# eMMC.net
KiCad netlist of a schematic drawn in Altium Designer
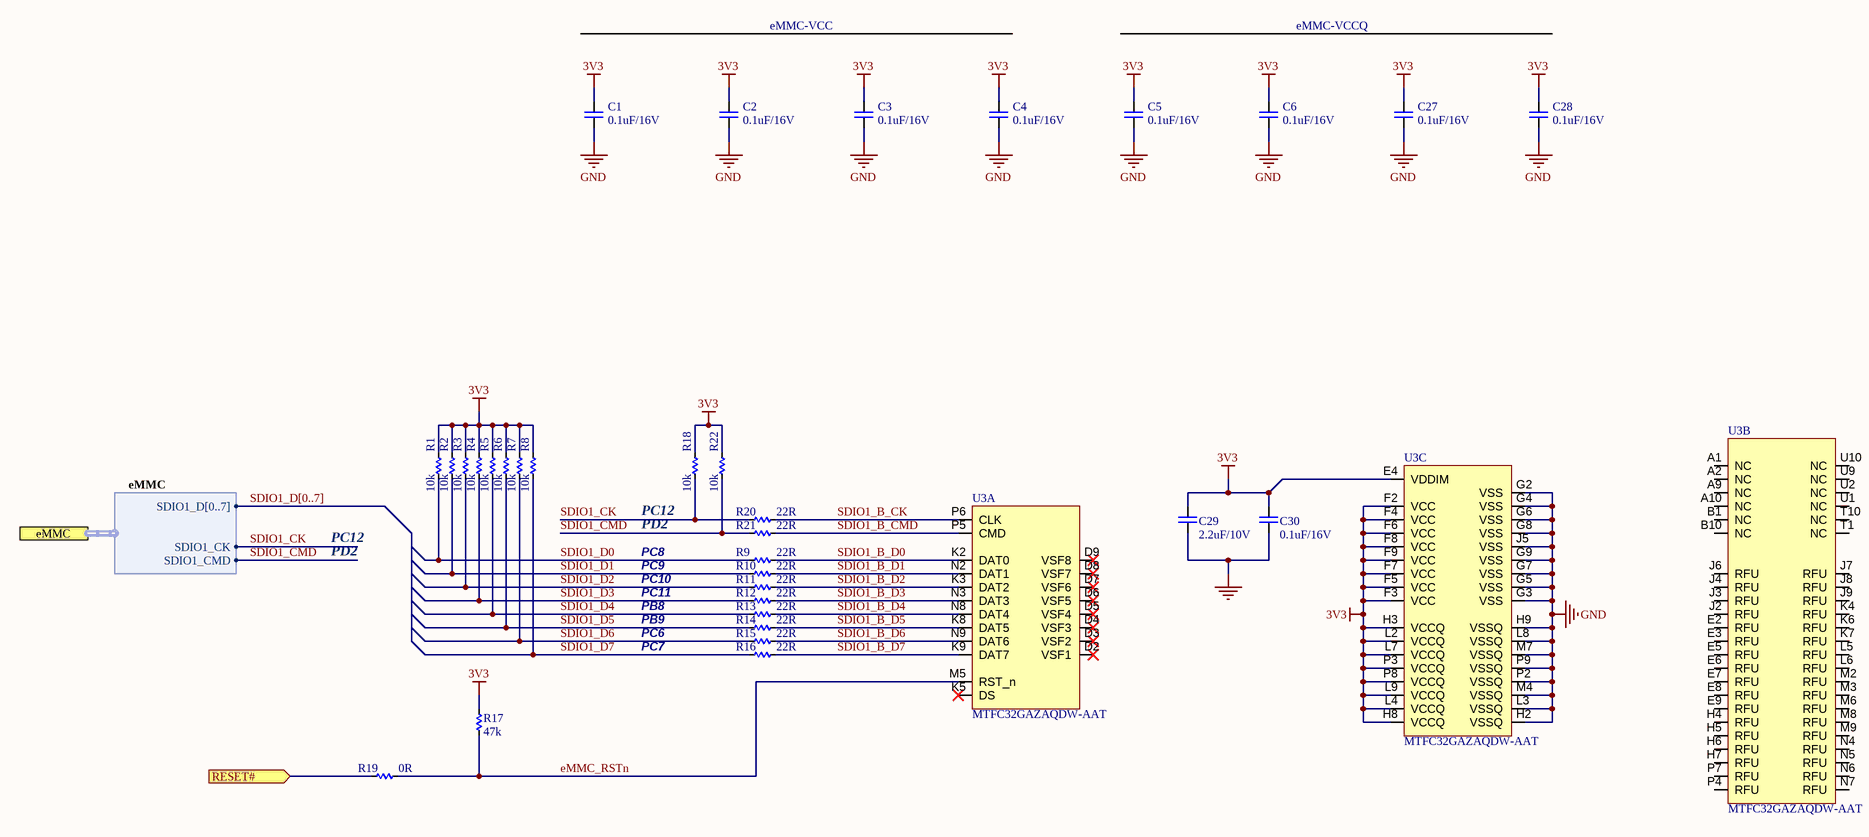
[diagram p0: eMMC.SchDoc]

(export (version "E")
  (design (tool "Eeschema 10.0.6"))
  (components
    (comp (ref "C1")
      (value "0.1uF/16V")
      (footprint "CAP_C_1608X80")
      (description "CAP_Chip")
      (libsource (lib "LABLIB") (part "CAP_SMD"))
    )
    (comp (ref "C2")
      (value "0.1uF/16V")
      (footprint "CAP_C_1608X80")
      (description "CAP_Chip")
      (libsource (lib "LABLIB") (part "CAP_SMD"))
    )
    (comp (ref "C3")
      (value "0.1uF/16V")
      (footprint "CAP_C_1608X80")
      (description "CAP_Chip")
      (libsource (lib "LABLIB") (part "CAP_SMD"))
    )
    (comp (ref "C4")
      (value "0.1uF/16V")
      (footprint "CAP_C_1608X80")
      (description "CAP_Chip")
      (libsource (lib "LABLIB") (part "CAP_SMD"))
    )
    (comp (ref "C5")
      (value "0.1uF/16V")
      (footprint "CAP_C_1608X80")
      (description "CAP_Chip")
      (libsource (lib "LABLIB") (part "CAP_SMD"))
    )
    (comp (ref "C6")
      (value "0.1uF/16V")
      (footprint "CAP_C_1608X80")
      (description "CAP_Chip")
      (libsource (lib "LABLIB") (part "CAP_SMD"))
    )
    (comp (ref "C27")
      (value "0.1uF/16V")
      (footprint "CAP_C_1608X80")
      (description "CAP_Chip")
      (libsource (lib "LABLIB") (part "CAP_SMD"))
    )
    (comp (ref "C28")
      (value "0.1uF/16V")
      (footprint "CAP_C_1608X80")
      (description "CAP_Chip")
      (libsource (lib "LABLIB") (part "CAP_SMD"))
    )
    (comp (ref "C29")
      (value "2.2uF/10V")
      (footprint "CAP_C_1608X80")
      (description "CAP_Chip")
      (libsource (lib "LABLIB") (part "CAP_SMD"))
    )
    (comp (ref "C30")
      (value "0.1uF/16V")
      (footprint "CAP_C_1608X80")
      (description "CAP_Chip")
      (libsource (lib "LABLIB") (part "CAP_SMD"))
    )
    (comp (ref "R1")
      (value "10k")
      (footprint "RES_C_1608X60")
      (description "RES")
      (libsource (lib "LABLIB") (part "_RES_B_2"))
    )
    (comp (ref "R2")
      (value "10k")
      (footprint "RES_C_1608X60")
      (description "RES")
      (libsource (lib "LABLIB") (part "_RES_B_2"))
    )
    (comp (ref "R3")
      (value "10k")
      (footprint "RES_C_1608X60")
      (description "RES")
      (libsource (lib "LABLIB") (part "_RES_B_2"))
    )
    (comp (ref "R4")
      (value "10k")
      (footprint "RES_C_1608X60")
      (description "RES")
      (libsource (lib "LABLIB") (part "_RES_B_2"))
    )
    (comp (ref "R5")
      (value "10k")
      (footprint "RES_C_1608X60")
      (description "RES")
      (libsource (lib "LABLIB") (part "_RES_B_2"))
    )
    (comp (ref "R6")
      (value "10k")
      (footprint "RES_C_1608X60")
      (description "RES")
      (libsource (lib "LABLIB") (part "_RES_B_2"))
    )
    (comp (ref "R7")
      (value "10k")
      (footprint "RES_C_1608X60")
      (description "RES")
      (libsource (lib "LABLIB") (part "_RES_B_2"))
    )
    (comp (ref "R8")
      (value "10k")
      (footprint "RES_C_1608X60")
      (description "RES")
      (libsource (lib "LABLIB") (part "_RES_B_2"))
    )
    (comp (ref "R9")
      (value "22R")
      (footprint "RES_C_1608X60")
      (description "RES")
      (libsource (lib "LABLIB") (part "_RES_B_2"))
    )
    (comp (ref "R10")
      (value "22R")
      (footprint "RES_C_1608X60")
      (description "RES")
      (libsource (lib "LABLIB") (part "_RES_B_2"))
    )
    (comp (ref "R11")
      (value "22R")
      (footprint "RES_C_1608X60")
      (description "RES")
      (libsource (lib "LABLIB") (part "_RES_B_2"))
    )
    (comp (ref "R12")
      (value "22R")
      (footprint "RES_C_1608X60")
      (description "RES")
      (libsource (lib "LABLIB") (part "_RES_B_2"))
    )
    (comp (ref "R13")
      (value "22R")
      (footprint "RES_C_1608X60")
      (description "RES")
      (libsource (lib "LABLIB") (part "_RES_B_2"))
    )
    (comp (ref "R14")
      (value "22R")
      (footprint "RES_C_1608X60")
      (description "RES")
      (libsource (lib "LABLIB") (part "_RES_B_2"))
    )
    (comp (ref "R15")
      (value "22R")
      (footprint "RES_C_1608X60")
      (description "RES")
      (libsource (lib "LABLIB") (part "_RES_B_2"))
    )
    (comp (ref "R16")
      (value "22R")
      (footprint "RES_C_1608X60")
      (description "RES")
      (libsource (lib "LABLIB") (part "_RES_B_2"))
    )
    (comp (ref "R17")
      (value "47k")
      (footprint "RES_C_1608X60")
      (description "RES")
      (libsource (lib "LABLIB") (part "_RES_B_2"))
    )
    (comp (ref "R18")
      (value "10k")
      (footprint "RES_C_1608X60")
      (description "RES")
      (libsource (lib "LABLIB") (part "_RES_B_2"))
    )
    (comp (ref "R19")
      (value "0R")
      (footprint "RES_C_1608X60")
      (description "RES")
      (libsource (lib "LABLIB") (part "_RES_B_2"))
    )
    (comp (ref "R20")
      (value "22R")
      (footprint "RES_C_1608X60")
      (description "RES")
      (libsource (lib "LABLIB") (part "_RES_B_2"))
    )
    (comp (ref "R21")
      (value "22R")
      (footprint "RES_C_1608X60")
      (description "RES")
      (libsource (lib "LABLIB") (part "_RES_B_2"))
    )
    (comp (ref "R22")
      (value "10k")
      (footprint "RES_C_1608X60")
      (description "RES")
      (libsource (lib "LABLIB") (part "_RES_B_2"))
    )
    (comp (ref "U3")
      (value "MTFC32GAZAQDW-AAT")
      (footprint "BGA_100_C_100P_10X17_1400X1800X150")
      (libsource (lib "COMM_SCHLIB") (part "MTFC32GAZAQDW-AAT"))
    )
  )
  (nets
    (net (code "2") (name "/RESET#") (class "Default")
      (node (ref "R19") (pin "2") (pinfunction "2_2") (pintype "passive"))
    )
    (net (code "3") (name "/SDIO1_B_CK") (class "Default")
      (node (ref "R20") (pin "2") (pinfunction "2_2") (pintype "passive"))
      (node (ref "U3") (pin "P6") (pinfunction "CLK_P6") (pintype "passive"))
    )
    (net (code "4") (name "/SDIO1_B_CMD") (class "Default")
      (node (ref "R21") (pin "2") (pinfunction "2_2") (pintype "passive"))
      (node (ref "U3") (pin "P5") (pinfunction "CMD_P5") (pintype "passive"))
    )
    (net (code "5") (name "/SDIO1_B_D0") (class "Default")
      (node (ref "R9") (pin "2") (pinfunction "2_2") (pintype "passive"))
      (node (ref "U3") (pin "K2") (pinfunction "DAT0_K2") (pintype "passive"))
    )
    (net (code "6") (name "/SDIO1_B_D1") (class "Default")
      (node (ref "R10") (pin "2") (pinfunction "2_2") (pintype "passive"))
      (node (ref "U3") (pin "N2") (pinfunction "DAT1_N2") (pintype "passive"))
    )
    (net (code "7") (name "/SDIO1_B_D2") (class "Default")
      (node (ref "R11") (pin "2") (pinfunction "2_2") (pintype "passive"))
      (node (ref "U3") (pin "K3") (pinfunction "DAT2_K3") (pintype "passive"))
    )
    (net (code "8") (name "/SDIO1_B_D3") (class "Default")
      (node (ref "R12") (pin "2") (pinfunction "2_2") (pintype "passive"))
      (node (ref "U3") (pin "N3") (pinfunction "DAT3_N3") (pintype "passive"))
    )
    (net (code "9") (name "/SDIO1_B_D4") (class "Default")
      (node (ref "R13") (pin "2") (pinfunction "2_2") (pintype "passive"))
      (node (ref "U3") (pin "N8") (pinfunction "DAT4_N8") (pintype "passive"))
    )
    (net (code "10") (name "/SDIO1_B_D5") (class "Default")
      (node (ref "R14") (pin "2") (pinfunction "2_2") (pintype "passive"))
      (node (ref "U3") (pin "K8") (pinfunction "DAT5_K8") (pintype "passive"))
    )
    (net (code "11") (name "/SDIO1_B_D6") (class "Default")
      (node (ref "R15") (pin "2") (pinfunction "2_2") (pintype "passive"))
      (node (ref "U3") (pin "N9") (pinfunction "DAT6_N9") (pintype "passive"))
    )
    (net (code "12") (name "/SDIO1_B_D7") (class "Default")
      (node (ref "R16") (pin "2") (pinfunction "2_2") (pintype "passive"))
      (node (ref "U3") (pin "K9") (pinfunction "DAT7_K9") (pintype "passive"))
    )
    (net (code "13") (name "/SDIO1_CK") (class "Default")
      (node (ref "R18") (pin "1") (pinfunction "1_1") (pintype "passive"))
      (node (ref "R20") (pin "1") (pinfunction "1_1") (pintype "passive"))
    )
    (net (code "14") (name "/SDIO1_CMD") (class "Default")
      (node (ref "R21") (pin "1") (pinfunction "1_1") (pintype "passive"))
      (node (ref "R22") (pin "1") (pinfunction "1_1") (pintype "passive"))
    )
    (net (code "15") (name "/SDIO1_D0") (class "Default")
      (node (ref "R1") (pin "1") (pinfunction "1_1") (pintype "passive"))
      (node (ref "R9") (pin "1") (pinfunction "1_1") (pintype "passive"))
    )
    (net (code "16") (name "/SDIO1_D1") (class "Default")
      (node (ref "R10") (pin "1") (pinfunction "1_1") (pintype "passive"))
      (node (ref "R2") (pin "1") (pinfunction "1_1") (pintype "passive"))
    )
    (net (code "17") (name "/SDIO1_D2") (class "Default")
      (node (ref "R11") (pin "1") (pinfunction "1_1") (pintype "passive"))
      (node (ref "R3") (pin "1") (pinfunction "1_1") (pintype "passive"))
    )
    (net (code "18") (name "/SDIO1_D3") (class "Default")
      (node (ref "R12") (pin "1") (pinfunction "1_1") (pintype "passive"))
      (node (ref "R4") (pin "1") (pinfunction "1_1") (pintype "passive"))
    )
    (net (code "19") (name "/SDIO1_D4") (class "Default")
      (node (ref "R13") (pin "1") (pinfunction "1_1") (pintype "passive"))
      (node (ref "R5") (pin "1") (pinfunction "1_1") (pintype "passive"))
    )
    (net (code "20") (name "/SDIO1_D5") (class "Default")
      (node (ref "R14") (pin "1") (pinfunction "1_1") (pintype "passive"))
      (node (ref "R6") (pin "1") (pinfunction "1_1") (pintype "passive"))
    )
    (net (code "21") (name "/SDIO1_D6") (class "Default")
      (node (ref "R15") (pin "1") (pinfunction "1_1") (pintype "passive"))
      (node (ref "R7") (pin "1") (pinfunction "1_1") (pintype "passive"))
    )
    (net (code "22") (name "/SDIO1_D7") (class "Default")
      (node (ref "R16") (pin "1") (pinfunction "1_1") (pintype "passive"))
      (node (ref "R8") (pin "1") (pinfunction "1_1") (pintype "passive"))
    )
    (net (code "23") (name "/eMMC_RSTn") (class "Default")
      (node (ref "R17") (pin "1") (pinfunction "1_1") (pintype "passive"))
      (node (ref "R19") (pin "1") (pinfunction "1_1") (pintype "passive"))
      (node (ref "U3") (pin "M5") (pinfunction "RST_n_M5") (pintype "passive"))
    )
    (net (code "26") (name "3V3") (class "Default")
      (node (ref "C1") (pin "2") (pinfunction "2_2") (pintype "passive"))
      (node (ref "C2") (pin "2") (pinfunction "2_2") (pintype "passive"))
      (node (ref "C27") (pin "2") (pinfunction "2_2") (pintype "passive"))
      (node (ref "C28") (pin "2") (pinfunction "2_2") (pintype "passive"))
      (node (ref "C29") (pin "2") (pinfunction "2_2") (pintype "passive"))
      (node (ref "C3") (pin "2") (pinfunction "2_2") (pintype "passive"))
      (node (ref "C30") (pin "2") (pinfunction "2_2") (pintype "passive"))
      (node (ref "C4") (pin "2") (pinfunction "2_2") (pintype "passive"))
      (node (ref "C5") (pin "2") (pinfunction "2_2") (pintype "passive"))
      (node (ref "C6") (pin "2") (pinfunction "2_2") (pintype "passive"))
      (node (ref "R1") (pin "2") (pinfunction "2_2") (pintype "passive"))
      (node (ref "R17") (pin "2") (pinfunction "2_2") (pintype "passive"))
      (node (ref "R18") (pin "2") (pinfunction "2_2") (pintype "passive"))
      (node (ref "R2") (pin "2") (pinfunction "2_2") (pintype "passive"))
      (node (ref "R22") (pin "2") (pinfunction "2_2") (pintype "passive"))
      (node (ref "R3") (pin "2") (pinfunction "2_2") (pintype "passive"))
      (node (ref "R4") (pin "2") (pinfunction "2_2") (pintype "passive"))
      (node (ref "R5") (pin "2") (pinfunction "2_2") (pintype "passive"))
      (node (ref "R6") (pin "2") (pinfunction "2_2") (pintype "passive"))
      (node (ref "R7") (pin "2") (pinfunction "2_2") (pintype "passive"))
      (node (ref "R8") (pin "2") (pinfunction "2_2") (pintype "passive"))
      (node (ref "U3") (pin "E4") (pinfunction "VDDIM_E4") (pintype "passive"))
      (node (ref "U3") (pin "F2") (pinfunction "VCC_F2") (pintype "passive"))
      (node (ref "U3") (pin "F3") (pinfunction "VCC_F3") (pintype "passive"))
      (node (ref "U3") (pin "F4") (pinfunction "VCC_F4") (pintype "passive"))
      (node (ref "U3") (pin "F5") (pinfunction "VCC_F5") (pintype "passive"))
      (node (ref "U3") (pin "F6") (pinfunction "VCC_F6") (pintype "passive"))
      (node (ref "U3") (pin "F7") (pinfunction "VCC_F7") (pintype "passive"))
      (node (ref "U3") (pin "F8") (pinfunction "VCC_F8") (pintype "passive"))
      (node (ref "U3") (pin "F9") (pinfunction "VCC_F9") (pintype "passive"))
      (node (ref "U3") (pin "H3") (pinfunction "VCCQ_H3") (pintype "passive"))
      (node (ref "U3") (pin "H8") (pinfunction "VCCQ_H8") (pintype "passive"))
      (node (ref "U3") (pin "L2") (pinfunction "VCCQ_L2") (pintype "passive"))
      (node (ref "U3") (pin "L4") (pinfunction "VCCQ_L4") (pintype "passive"))
      (node (ref "U3") (pin "L7") (pinfunction "VCCQ_L7") (pintype "passive"))
      (node (ref "U3") (pin "L9") (pinfunction "VCCQ_L9") (pintype "passive"))
      (node (ref "U3") (pin "P3") (pinfunction "VCCQ_P3") (pintype "passive"))
      (node (ref "U3") (pin "P8") (pinfunction "VCCQ_P8") (pintype "passive"))
    )
    (net (code "27") (name "GND") (class "Default")
      (node (ref "C1") (pin "1") (pinfunction "1_1") (pintype "passive"))
      (node (ref "C2") (pin "1") (pinfunction "1_1") (pintype "passive"))
      (node (ref "C27") (pin "1") (pinfunction "1_1") (pintype "passive"))
      (node (ref "C28") (pin "1") (pinfunction "1_1") (pintype "passive"))
      (node (ref "C29") (pin "1") (pinfunction "1_1") (pintype "passive"))
      (node (ref "C3") (pin "1") (pinfunction "1_1") (pintype "passive"))
      (node (ref "C30") (pin "1") (pinfunction "1_1") (pintype "passive"))
      (node (ref "C4") (pin "1") (pinfunction "1_1") (pintype "passive"))
      (node (ref "C5") (pin "1") (pinfunction "1_1") (pintype "passive"))
      (node (ref "C6") (pin "1") (pinfunction "1_1") (pintype "passive"))
      (node (ref "U3") (pin "G2") (pinfunction "VSS_G2") (pintype "passive"))
      (node (ref "U3") (pin "G3") (pinfunction "VSS_G3") (pintype "passive"))
      (node (ref "U3") (pin "G4") (pinfunction "VSS_G4") (pintype "passive"))
      (node (ref "U3") (pin "G5") (pinfunction "VSS_G5") (pintype "passive"))
      (node (ref "U3") (pin "G6") (pinfunction "VSS_G6") (pintype "passive"))
      (node (ref "U3") (pin "G7") (pinfunction "VSS_G7") (pintype "passive"))
      (node (ref "U3") (pin "G8") (pinfunction "VSS_G8") (pintype "passive"))
      (node (ref "U3") (pin "G9") (pinfunction "VSS_G9") (pintype "passive"))
      (node (ref "U3") (pin "H2") (pinfunction "VSSQ_H2") (pintype "passive"))
      (node (ref "U3") (pin "H9") (pinfunction "VSSQ_H9") (pintype "passive"))
      (node (ref "U3") (pin "J5") (pinfunction "VSS_J5") (pintype "passive"))
      (node (ref "U3") (pin "L3") (pinfunction "VSSQ_L3") (pintype "passive"))
      (node (ref "U3") (pin "L8") (pinfunction "VSSQ_L8") (pintype "passive"))
      (node (ref "U3") (pin "M4") (pinfunction "VSSQ_M4") (pintype "passive"))
      (node (ref "U3") (pin "M7") (pinfunction "VSSQ_M7") (pintype "passive"))
      (node (ref "U3") (pin "P2") (pinfunction "VSSQ_P2") (pintype "passive"))
      (node (ref "U3") (pin "P9") (pinfunction "VSSQ_P9") (pintype "passive"))
    )
    (net (code "28") (name "unconnected-(U3A-DS-PadK5)") (class "Default")
      (node (ref "U3") (pin "K5") (pinfunction "DS_K5") (pintype "passive+no_connect"))
    )
    (net (code "29") (name "unconnected-(U3A-VSF1-PadD2)") (class "Default")
      (node (ref "U3") (pin "D2") (pinfunction "VSF1_D2") (pintype "passive+no_connect"))
    )
    (net (code "30") (name "unconnected-(U3A-VSF2-PadD3)") (class "Default")
      (node (ref "U3") (pin "D3") (pinfunction "VSF2_D3") (pintype "passive+no_connect"))
    )
    (net (code "31") (name "unconnected-(U3A-VSF3-PadD4)") (class "Default")
      (node (ref "U3") (pin "D4") (pinfunction "VSF3_D4") (pintype "passive+no_connect"))
    )
    (net (code "32") (name "unconnected-(U3A-VSF4-PadD5)") (class "Default")
      (node (ref "U3") (pin "D5") (pinfunction "VSF4_D5") (pintype "passive+no_connect"))
    )
    (net (code "33") (name "unconnected-(U3A-VSF5-PadD6)") (class "Default")
      (node (ref "U3") (pin "D6") (pinfunction "VSF5_D6") (pintype "passive+no_connect"))
    )
    (net (code "34") (name "unconnected-(U3A-VSF6-PadD7)") (class "Default")
      (node (ref "U3") (pin "D7") (pinfunction "VSF6_D7") (pintype "passive+no_connect"))
    )
    (net (code "35") (name "unconnected-(U3A-VSF7-PadD8)") (class "Default")
      (node (ref "U3") (pin "D8") (pinfunction "VSF7_D8") (pintype "passive+no_connect"))
    )
    (net (code "36") (name "unconnected-(U3A-VSF8-PadD9)") (class "Default")
      (node (ref "U3") (pin "D9") (pinfunction "VSF8_D9") (pintype "passive+no_connect"))
    )
    (net (code "37") (name "unconnected-(U3B-NC-PadA1)") (class "Default")
      (node (ref "U3") (pin "A1") (pinfunction "NC_A1") (pintype "passive"))
    )
    (net (code "38") (name "unconnected-(U3B-NC-PadA2)") (class "Default")
      (node (ref "U3") (pin "A2") (pinfunction "NC_A2") (pintype "passive"))
    )
    (net (code "39") (name "unconnected-(U3B-NC-PadA9)") (class "Default")
      (node (ref "U3") (pin "A9") (pinfunction "NC_A9") (pintype "passive"))
    )
    (net (code "40") (name "unconnected-(U3B-NC-PadA10)") (class "Default")
      (node (ref "U3") (pin "A10") (pinfunction "NC_A10") (pintype "passive"))
    )
    (net (code "41") (name "unconnected-(U3B-NC-PadB1)") (class "Default")
      (node (ref "U3") (pin "B1") (pinfunction "NC_B1") (pintype "passive"))
    )
    (net (code "42") (name "unconnected-(U3B-NC-PadB10)") (class "Default")
      (node (ref "U3") (pin "B10") (pinfunction "NC_B10") (pintype "passive"))
    )
    (net (code "43") (name "unconnected-(U3B-NC-PadT1)") (class "Default")
      (node (ref "U3") (pin "T1") (pinfunction "NC_T1") (pintype "passive"))
    )
    (net (code "44") (name "unconnected-(U3B-NC-PadT10)") (class "Default")
      (node (ref "U3") (pin "T10") (pinfunction "NC_T10") (pintype "passive"))
    )
    (net (code "45") (name "unconnected-(U3B-NC-PadU1)") (class "Default")
      (node (ref "U3") (pin "U1") (pinfunction "NC_U1") (pintype "passive"))
    )
    (net (code "46") (name "unconnected-(U3B-NC-PadU2)") (class "Default")
      (node (ref "U3") (pin "U2") (pinfunction "NC_U2") (pintype "passive"))
    )
    (net (code "47") (name "unconnected-(U3B-NC-PadU9)") (class "Default")
      (node (ref "U3") (pin "U9") (pinfunction "NC_U9") (pintype "passive"))
    )
    (net (code "48") (name "unconnected-(U3B-NC-PadU10)") (class "Default")
      (node (ref "U3") (pin "U10") (pinfunction "NC_U10") (pintype "passive"))
    )
    (net (code "49") (name "unconnected-(U3B-RFU-PadE2)") (class "Default")
      (node (ref "U3") (pin "E2") (pinfunction "RFU_E2") (pintype "passive"))
    )
    (net (code "50") (name "unconnected-(U3B-RFU-PadE3)") (class "Default")
      (node (ref "U3") (pin "E3") (pinfunction "RFU_E3") (pintype "passive"))
    )
    (net (code "51") (name "unconnected-(U3B-RFU-PadE5)") (class "Default")
      (node (ref "U3") (pin "E5") (pinfunction "RFU_E5") (pintype "passive"))
    )
    (net (code "52") (name "unconnected-(U3B-RFU-PadE6)") (class "Default")
      (node (ref "U3") (pin "E6") (pinfunction "RFU_E6") (pintype "passive"))
    )
    (net (code "53") (name "unconnected-(U3B-RFU-PadE7)") (class "Default")
      (node (ref "U3") (pin "E7") (pinfunction "RFU_E7") (pintype "passive"))
    )
    (net (code "54") (name "unconnected-(U3B-RFU-PadE8)") (class "Default")
      (node (ref "U3") (pin "E8") (pinfunction "RFU_E8") (pintype "passive"))
    )
    (net (code "55") (name "unconnected-(U3B-RFU-PadE9)") (class "Default")
      (node (ref "U3") (pin "E9") (pinfunction "RFU_E9") (pintype "passive"))
    )
    (net (code "56") (name "unconnected-(U3B-RFU-PadH4)") (class "Default")
      (node (ref "U3") (pin "H4") (pinfunction "RFU_H4") (pintype "passive"))
    )
    (net (code "57") (name "unconnected-(U3B-RFU-PadH5)") (class "Default")
      (node (ref "U3") (pin "H5") (pinfunction "RFU_H5") (pintype "passive"))
    )
    (net (code "58") (name "unconnected-(U3B-RFU-PadH6)") (class "Default")
      (node (ref "U3") (pin "H6") (pinfunction "RFU_H6") (pintype "passive"))
    )
    (net (code "59") (name "unconnected-(U3B-RFU-PadH7)") (class "Default")
      (node (ref "U3") (pin "H7") (pinfunction "RFU_H7") (pintype "passive"))
    )
    (net (code "60") (name "unconnected-(U3B-RFU-PadJ2)") (class "Default")
      (node (ref "U3") (pin "J2") (pinfunction "RFU_J2") (pintype "passive"))
    )
    (net (code "61") (name "unconnected-(U3B-RFU-PadJ3)") (class "Default")
      (node (ref "U3") (pin "J3") (pinfunction "RFU_J3") (pintype "passive"))
    )
    (net (code "62") (name "unconnected-(U3B-RFU-PadJ4)") (class "Default")
      (node (ref "U3") (pin "J4") (pinfunction "RFU_J4") (pintype "passive"))
    )
    (net (code "63") (name "unconnected-(U3B-RFU-PadJ6)") (class "Default")
      (node (ref "U3") (pin "J6") (pinfunction "RFU_J6") (pintype "passive"))
    )
    (net (code "64") (name "unconnected-(U3B-RFU-PadJ7)") (class "Default")
      (node (ref "U3") (pin "J7") (pinfunction "RFU_J7") (pintype "passive"))
    )
    (net (code "65") (name "unconnected-(U3B-RFU-PadJ8)") (class "Default")
      (node (ref "U3") (pin "J8") (pinfunction "RFU_J8") (pintype "passive"))
    )
    (net (code "66") (name "unconnected-(U3B-RFU-PadJ9)") (class "Default")
      (node (ref "U3") (pin "J9") (pinfunction "RFU_J9") (pintype "passive"))
    )
    (net (code "67") (name "unconnected-(U3B-RFU-PadK4)") (class "Default")
      (node (ref "U3") (pin "K4") (pinfunction "RFU_K4") (pintype "passive"))
    )
    (net (code "68") (name "unconnected-(U3B-RFU-PadK6)") (class "Default")
      (node (ref "U3") (pin "K6") (pinfunction "RFU_K6") (pintype "passive"))
    )
    (net (code "69") (name "unconnected-(U3B-RFU-PadK7)") (class "Default")
      (node (ref "U3") (pin "K7") (pinfunction "RFU_K7") (pintype "passive"))
    )
    (net (code "70") (name "unconnected-(U3B-RFU-PadL5)") (class "Default")
      (node (ref "U3") (pin "L5") (pinfunction "RFU_L5") (pintype "passive"))
    )
    (net (code "71") (name "unconnected-(U3B-RFU-PadL6)") (class "Default")
      (node (ref "U3") (pin "L6") (pinfunction "RFU_L6") (pintype "passive"))
    )
    (net (code "72") (name "unconnected-(U3B-RFU-PadM2)") (class "Default")
      (node (ref "U3") (pin "M2") (pinfunction "RFU_M2") (pintype "passive"))
    )
    (net (code "73") (name "unconnected-(U3B-RFU-PadM3)") (class "Default")
      (node (ref "U3") (pin "M3") (pinfunction "RFU_M3") (pintype "passive"))
    )
    (net (code "74") (name "unconnected-(U3B-RFU-PadM6)") (class "Default")
      (node (ref "U3") (pin "M6") (pinfunction "RFU_M6") (pintype "passive"))
    )
    (net (code "75") (name "unconnected-(U3B-RFU-PadM8)") (class "Default")
      (node (ref "U3") (pin "M8") (pinfunction "RFU_M8") (pintype "passive"))
    )
    (net (code "76") (name "unconnected-(U3B-RFU-PadM9)") (class "Default")
      (node (ref "U3") (pin "M9") (pinfunction "RFU_M9") (pintype "passive"))
    )
    (net (code "77") (name "unconnected-(U3B-RFU-PadN4)") (class "Default")
      (node (ref "U3") (pin "N4") (pinfunction "RFU_N4") (pintype "passive"))
    )
    (net (code "78") (name "unconnected-(U3B-RFU-PadN5)") (class "Default")
      (node (ref "U3") (pin "N5") (pinfunction "RFU_N5") (pintype "passive"))
    )
    (net (code "79") (name "unconnected-(U3B-RFU-PadN6)") (class "Default")
      (node (ref "U3") (pin "N6") (pinfunction "RFU_N6") (pintype "passive"))
    )
    (net (code "80") (name "unconnected-(U3B-RFU-PadN7)") (class "Default")
      (node (ref "U3") (pin "N7") (pinfunction "RFU_N7") (pintype "passive"))
    )
    (net (code "81") (name "unconnected-(U3B-RFU-PadP4)") (class "Default")
      (node (ref "U3") (pin "P4") (pinfunction "RFU_P4") (pintype "passive"))
    )
    (net (code "82") (name "unconnected-(U3B-RFU-PadP7)") (class "Default")
      (node (ref "U3") (pin "P7") (pinfunction "RFU_P7") (pintype "passive"))
    )
  )
)
